# RS485_INTERFACE.net
KiCad netlist of a schematic drawn in Altium Designer
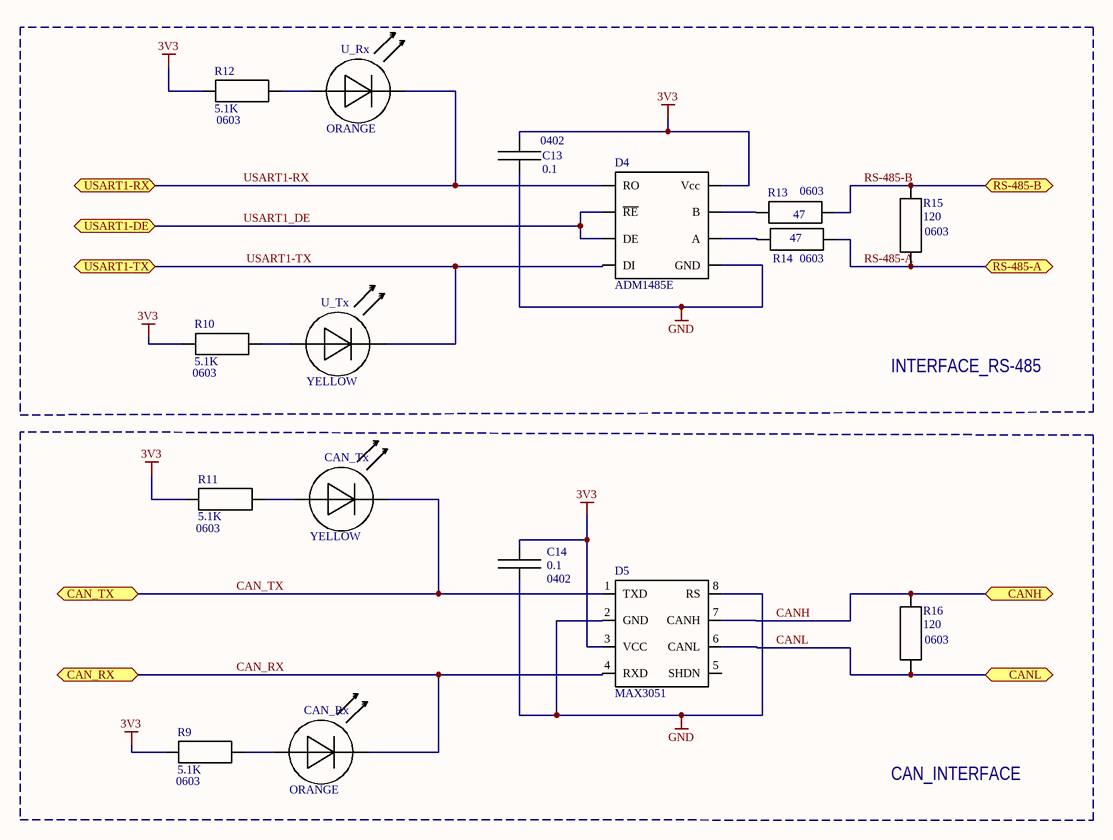
[diagram p0: RS485_INTERFACE.SchDoc]

(export (version "E")
  (design (tool "Eeschema 10.0.6"))
  (components
    (comp (ref "C13")
      (value "0.1")
      (footprint "Mylibrary:SMD_0402_C")
      (libsource (lib "Mylibrary") (part "Capacitor"))
    )
    (comp (ref "C14")
      (value "0.1")
      (footprint "Mylibrary:SMD_0402_C")
      (libsource (lib "Mylibrary") (part "Capacitor"))
    )
    (comp (ref "CAN_Rx")
      (value "ORANGE")
      (footprint "Mylibrary:SMD_LED_2012")
      (libsource (lib "Mylibrary") (part "LED_Diode"))
    )
    (comp (ref "CAN_Tx")
      (value "YELLOW")
      (footprint "Mylibrary:SMD_LED")
      (libsource (lib "Mylibrary") (part "LED_Diode"))
    )
    (comp (ref "D4")
      (value "ADM1485E")
      (footprint "Mylibrary:SOIC_N 8-Lead")
      (libsource (lib "Mylibrary") (part "ADM1485E"))
    )
    (comp (ref "D5")
      (value "MAX3051")
      (footprint "Mylibrary:SOIC_N 8-Lead")
      (description "CAN Transeiver, 3.3V, 1Mbps, 8pin")
      (libsource (lib "Mylibrary") (part "MAX3051"))
    )
    (comp (ref "R9")
      (value "5.1K")
      (footprint "SMD_0603")
      (description "0603 resistor")
      (libsource (lib "Mylibrary") (part "Resistor"))
    )
    (comp (ref "R10")
      (value "5.1K")
      (footprint "SMD_0603")
      (description "0603 resistor")
      (libsource (lib "Mylibrary") (part "Resistor"))
    )
    (comp (ref "R11")
      (value "5.1K")
      (footprint "SMD_0603")
      (description "0603 resistor")
      (libsource (lib "Mylibrary") (part "Resistor"))
    )
    (comp (ref "R12")
      (value "5.1K")
      (footprint "SMD_0603")
      (description "0603 resistor")
      (libsource (lib "Mylibrary") (part "Resistor"))
    )
    (comp (ref "R13") (value "47") (footprint "SMD_0603") (libsource (lib "Mylibrary") (part "Resistor")))
    (comp (ref "R14") (value "47") (footprint "SMD_0603") (libsource (lib "Mylibrary") (part "Resistor")))
    (comp (ref "R15") (value "120") (footprint "SMD_0603") (libsource (lib "Mylibrary") (part "Resistor")))
    (comp (ref "R16")
      (value "120")
      (footprint "SMD_0603")
      (description "0603 resistor")
      (libsource (lib "Mylibrary") (part "Resistor"))
    )
    (comp (ref "U_Rx")
      (value "ORANGE")
      (footprint "Mylibrary:SMD_LED_2012")
      (libsource (lib "Mylibrary") (part "LED_Diode"))
    )
    (comp (ref "U_Tx")
      (value "YELLOW")
      (footprint "Mylibrary:SMD_LED")
      (libsource (lib "Mylibrary") (part "LED_Diode"))
    )
  )
  (nets
    (net (code "1") (name "/CANH") (class "Default")
      (node (ref "D5") (pin "7") (pinfunction "CANH_7") (pintype "passive"))
      (node (ref "R16") (pin "2") (pinfunction "2_2") (pintype "passive"))
    )
    (net (code "2") (name "/CANL") (class "Default")
      (node (ref "D5") (pin "6") (pinfunction "CANL_6") (pintype "passive"))
      (node (ref "R16") (pin "1") (pinfunction "1_1") (pintype "passive"))
    )
    (net (code "3") (name "/CAN_RX") (class "Default")
      (node (ref "CAN_Rx") (pin "1") (pintype "passive"))
      (node (ref "D5") (pin "4") (pinfunction "RXD_4") (pintype "passive"))
    )
    (net (code "4") (name "/CAN_TX") (class "Default")
      (node (ref "CAN_Tx") (pin "1") (pintype "passive"))
      (node (ref "D5") (pin "1") (pinfunction "TXD_1") (pintype "passive"))
    )
    (net (code "5") (name "/RS-485-A") (class "Default")
      (node (ref "R14") (pin "2") (pinfunction "2_2") (pintype "passive"))
      (node (ref "R15") (pin "1") (pinfunction "1_1") (pintype "passive"))
    )
    (net (code "6") (name "/RS-485-B") (class "Default")
      (node (ref "R13") (pin "2") (pinfunction "2_2") (pintype "passive"))
      (node (ref "R15") (pin "2") (pinfunction "2_2") (pintype "passive"))
    )
    (net (code "7") (name "/USART1-RX") (class "Default")
      (node (ref "D4") (pin "1") (pinfunction "RO_1") (pintype "passive"))
      (node (ref "U_Rx") (pin "1") (pintype "passive"))
    )
    (net (code "8") (name "/USART1-TX") (class "Default")
      (node (ref "D4") (pin "4") (pinfunction "DI_4") (pintype "passive"))
      (node (ref "U_Tx") (pin "1") (pintype "passive"))
    )
    (net (code "9") (name "/USART1_DE") (class "Default")
      (node (ref "D4") (pin "2") (pinfunction "~{RE}_2") (pintype "passive"))
      (node (ref "D4") (pin "3") (pinfunction "DE_3") (pintype "passive"))
    )
    (net (code "10") (name "3V3") (class "Default")
      (node (ref "C13") (pin "2") (pinfunction "2_2") (pintype "passive"))
      (node (ref "C14") (pin "2") (pinfunction "2_2") (pintype "passive"))
      (node (ref "D4") (pin "8") (pinfunction "Vcc_8") (pintype "passive"))
      (node (ref "D5") (pin "3") (pinfunction "VCC_3") (pintype "passive"))
      (node (ref "R10") (pin "1") (pinfunction "1_1") (pintype "passive"))
      (node (ref "R11") (pin "1") (pinfunction "1_1") (pintype "passive"))
      (node (ref "R12") (pin "1") (pinfunction "1_1") (pintype "passive"))
      (node (ref "R9") (pin "1") (pinfunction "1_1") (pintype "passive"))
    )
    (net (code "11") (name "GND") (class "Default")
      (node (ref "C13") (pin "1") (pinfunction "1_1") (pintype "passive"))
      (node (ref "C14") (pin "1") (pinfunction "1_1") (pintype "passive"))
      (node (ref "D4") (pin "5") (pinfunction "GND_5") (pintype "passive"))
      (node (ref "D5") (pin "2") (pinfunction "GND_2") (pintype "passive"))
      (node (ref "D5") (pin "8") (pinfunction "RS_8") (pintype "passive"))
    )
    (net (code "12") (name "Net-(CAN_Rx-Pad2)") (class "Default")
      (node (ref "CAN_Rx") (pin "2") (pintype "passive"))
      (node (ref "R9") (pin "2") (pinfunction "2_2") (pintype "passive"))
    )
    (net (code "13") (name "Net-(CAN_Tx-Pad2)") (class "Default")
      (node (ref "CAN_Tx") (pin "2") (pintype "passive"))
      (node (ref "R11") (pin "2") (pinfunction "2_2") (pintype "passive"))
    )
    (net (code "14") (name "Net-(D4-A)") (class "Default")
      (node (ref "D4") (pin "6") (pinfunction "A_6") (pintype "passive"))
      (node (ref "R14") (pin "1") (pinfunction "1_1") (pintype "passive"))
    )
    (net (code "15") (name "Net-(D4-B)") (class "Default")
      (node (ref "D4") (pin "7") (pinfunction "B_7") (pintype "passive"))
      (node (ref "R13") (pin "1") (pinfunction "1_1") (pintype "passive"))
    )
    (net (code "16") (name "Net-(R10-Pad2)") (class "Default")
      (node (ref "R10") (pin "2") (pinfunction "2_2") (pintype "passive"))
      (node (ref "U_Tx") (pin "2") (pintype "passive"))
    )
    (net (code "17") (name "Net-(R12-Pad2)") (class "Default")
      (node (ref "R12") (pin "2") (pinfunction "2_2") (pintype "passive"))
      (node (ref "U_Rx") (pin "2") (pintype "passive"))
    )
    (net (code "18") (name "unconnected-(D5-SHDN-Pad5)") (class "Default")
      (node (ref "D5") (pin "5") (pinfunction "SHDN_5") (pintype "passive"))
    )
  )
)
